# POWER_SENSING.net
KiCad netlist of a schematic drawn in Altium Designer
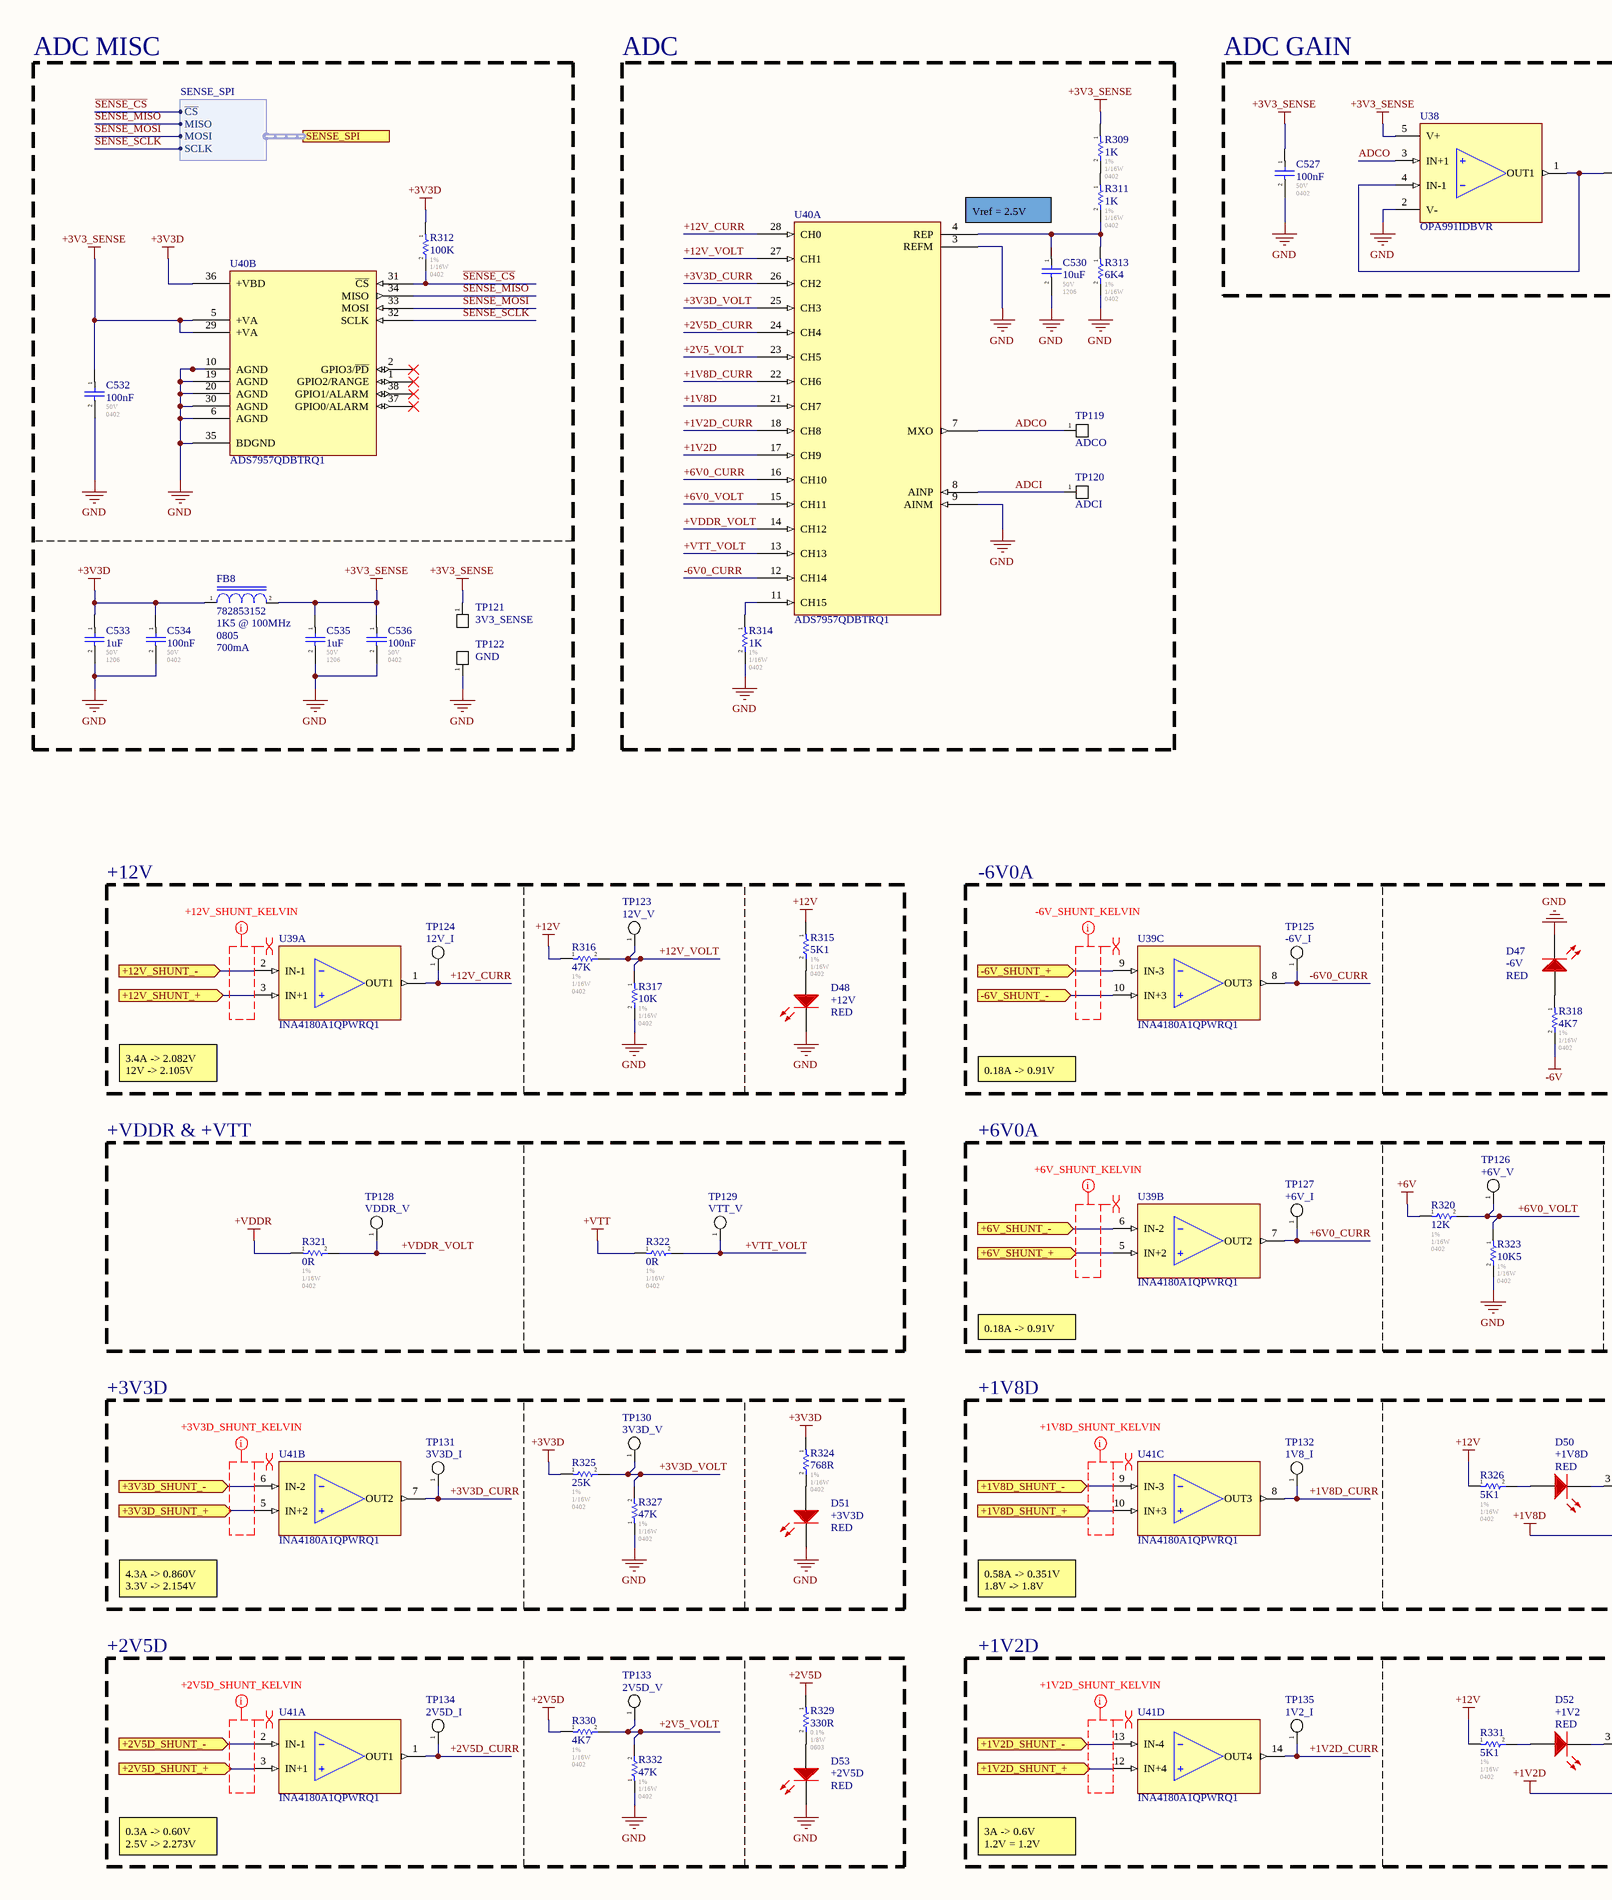
[diagram p0: POWER_SENSING.SchDoc, left]
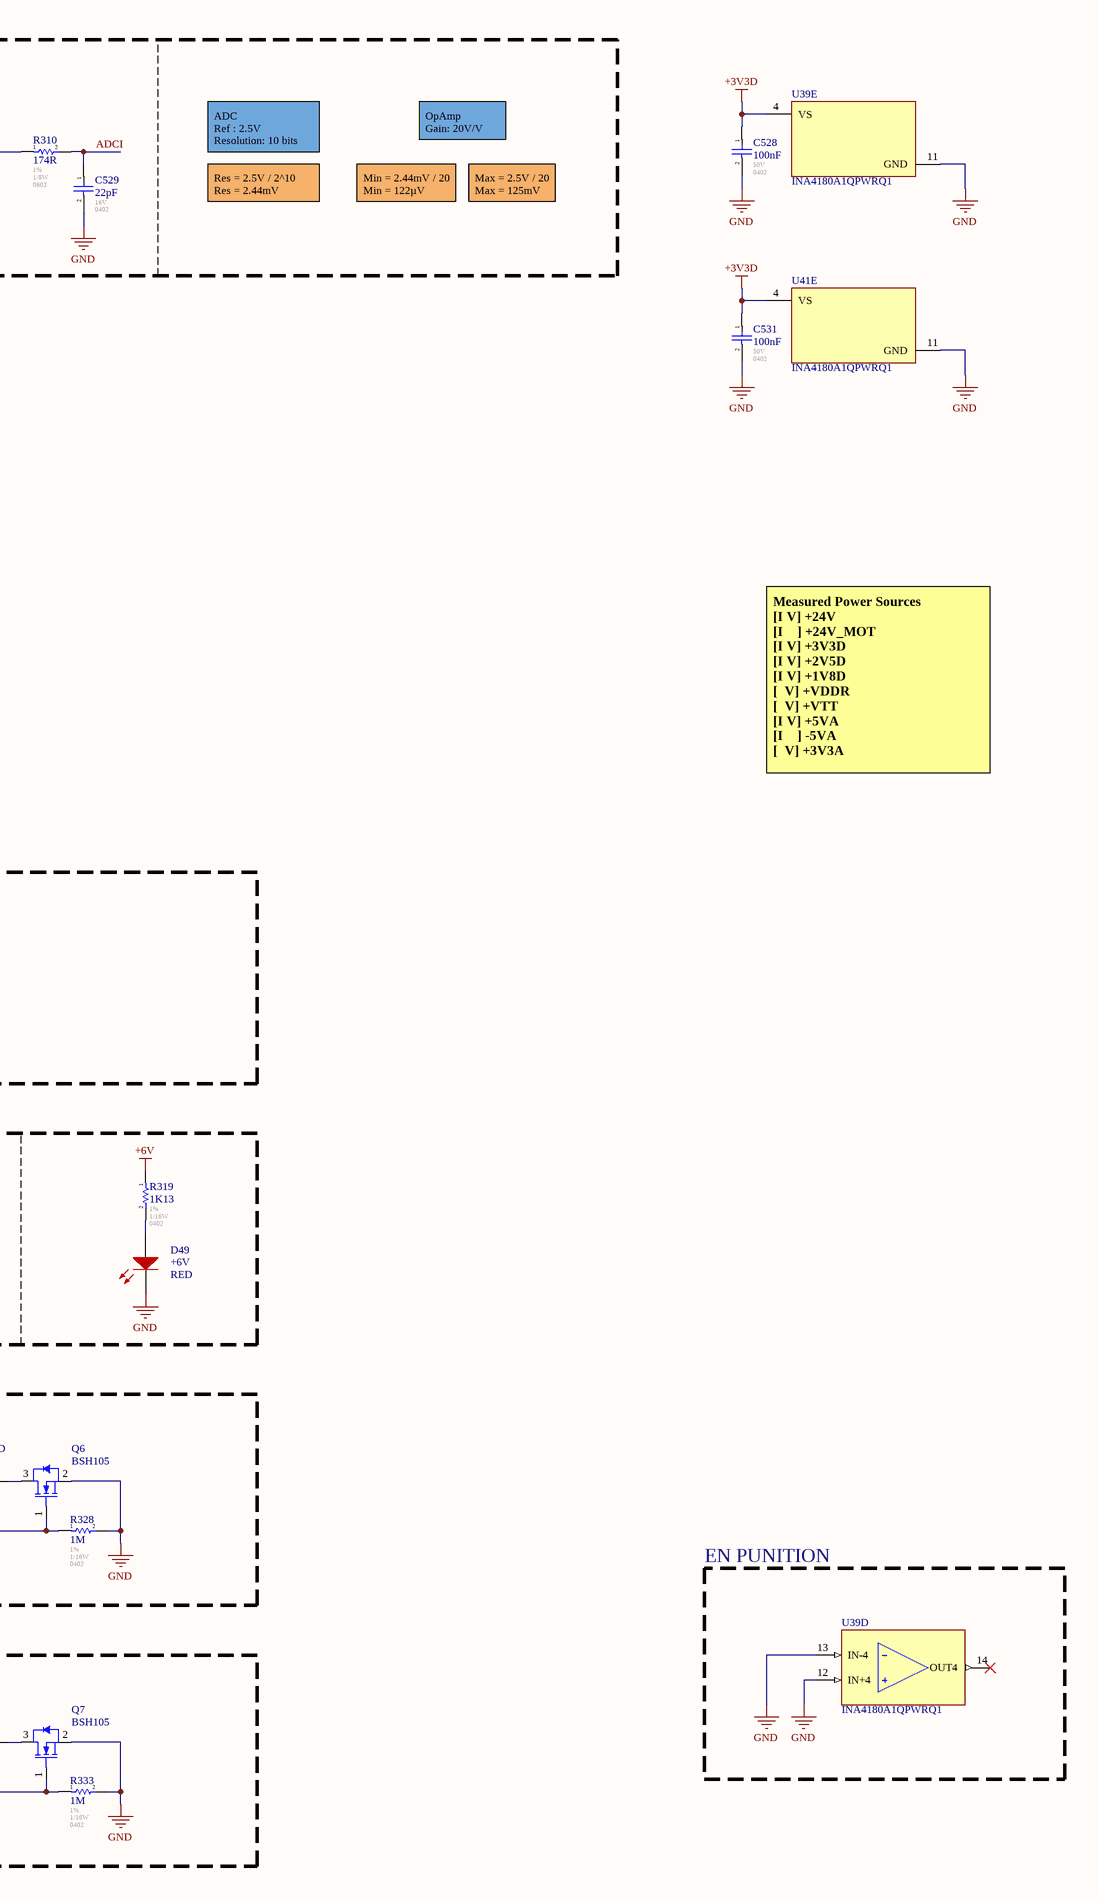
[diagram p1: POWER_SENSING.SchDoc, right]

(export (version "E")
  (design (tool "Eeschema 10.0.6"))
  (components
    (comp (ref "C527")
      (value "100nF")
      (footprint "0402")
      (description "GCM155R71H104KE02J\r\n0402 100nF 10% X7R Ceramic Capacitor")
      (fields
        (field (name "MFR") "Murata")
        (field (name "PART#") "GCM155R71H104KE02J")
        (field (name "VOLTAGE - RATED") "50V")
      )
      (libsource (lib "Symbols") (part "CAP_CER"))
    )
    (comp (ref "C528")
      (value "100nF")
      (footprint "0402")
      (description "GCM155R71H104KE02J\r\n0402 100nF 10% X7R Ceramic Capacitor")
      (fields
        (field (name "MFR") "Murata")
        (field (name "PART#") "GCM155R71H104KE02J")
        (field (name "VOLTAGE - RATED") "50V")
      )
      (libsource (lib "Symbols") (part "CAP_CER"))
    )
    (comp (ref "C529")
      (value "22pF")
      (footprint "0402")
      (description "0402 22pF 10% X7R 16V Ceramic Capacitor\r\nC0402C220K4RACAUTO")
      (fields
        (field (name "MFR") "KEMET")
        (field (name "PART#") "C0402C220K4RACAUTO")
        (field (name "VOLTAGE - RATED") "16V")
      )
      (libsource (lib "Symbols") (part "CAP_CER"))
    )
    (comp (ref "C530")
      (value "10uF")
      (footprint "1206")
      (description "GRT31CR61H106KE01L\r\n1206 10uF 10% X5R Ceramic Capacitor")
      (fields
        (field (name "MFR") "Murata")
        (field (name "VOLTAGE - RATED") "50V")
        (field (name "TOLERANCE") "10%")
      )
      (libsource (lib "Symbols") (part "CAP_CER"))
    )
    (comp (ref "C531")
      (value "100nF")
      (footprint "0402")
      (description "GCM155R71H104KE02J\r\n0402 100nF 10% X7R Ceramic Capacitor")
      (fields
        (field (name "MFR") "Murata")
        (field (name "PART#") "GCM155R71H104KE02J")
        (field (name "VOLTAGE - RATED") "50V")
      )
      (libsource (lib "Symbols") (part "CAP_CER"))
    )
    (comp (ref "C532")
      (value "100nF")
      (footprint "0402")
      (description "GCM155R71H104KE02J\r\n0402 100nF 10% X7R Ceramic Capacitor")
      (fields
        (field (name "MFR") "Murata")
        (field (name "PART#") "GCM155R71H104KE02J")
        (field (name "VOLTAGE - RATED") "50V")
      )
      (libsource (lib "Symbols") (part "CAP_CER"))
    )
    (comp (ref "C533")
      (value "1uF")
      (footprint "1206")
      (description "GCJ31CR71H105KA12L\r\n1206 1uF 10% X7R Ceramic Capacitor")
      (fields
        (field (name "MFR") "Murata")
        (field (name "PART#") "GCJ31CR71H105KA12L")
        (field (name "VOLTAGE - RATED") "50V")
      )
      (libsource (lib "Symbols") (part "CAP_CER"))
    )
    (comp (ref "C534")
      (value "100nF")
      (footprint "0402")
      (description "GCM155R71H104KE02J\r\n0402 100nF 10% X7R Ceramic Capacitor")
      (fields
        (field (name "MFR") "Murata")
        (field (name "PART#") "GCM155R71H104KE02J")
        (field (name "VOLTAGE - RATED") "50V")
      )
      (libsource (lib "Symbols") (part "CAP_CER"))
    )
    (comp (ref "C535")
      (value "1uF")
      (footprint "1206")
      (description "GCJ31CR71H105KA12L\r\n1206 1uF 10% X7R Ceramic Capacitor")
      (fields
        (field (name "MFR") "Murata")
        (field (name "PART#") "GCJ31CR71H105KA12L")
        (field (name "VOLTAGE - RATED") "50V")
      )
      (libsource (lib "Symbols") (part "CAP_CER"))
    )
    (comp (ref "C536")
      (value "100nF")
      (footprint "0402")
      (description "GCM155R71H104KE02J\r\n0402 100nF 10% X7R Ceramic Capacitor")
      (fields
        (field (name "MFR") "Murata")
        (field (name "PART#") "GCM155R71H104KE02J")
        (field (name "VOLTAGE - RATED") "50V")
      )
      (libsource (lib "Symbols") (part "CAP_CER"))
    )
    (comp (ref "D47")
      (value "-6V")
      (footprint "LED_0603")
      (description "LED - 620nM RED 2mA - 0603")
      (fields
        (field (name "VOLTAGE") "1.8V")
        (field (name "MFG") "ROHM Semiconductor")
        (field (name "ALTIUM_VALUE") "RED")
        (field (name "CREATEDBY") "Jonathan Bouchard")
      )
      (libsource (lib "S7CAS_LIB2023") (part "LED_SML-311UTT86"))
    )
    (comp (ref "D48")
      (value "+12V")
      (footprint "LED_0603")
      (description "LED - 620nM RED 2mA - 0603")
      (fields
        (field (name "VOLTAGE") "1.8V")
        (field (name "MFG") "ROHM Semiconductor")
        (field (name "ALTIUM_VALUE") "RED")
        (field (name "CREATEDBY") "Jonathan Bouchard")
      )
      (libsource (lib "S7CAS_LIB2023") (part "LED_SML-311UTT86"))
    )
    (comp (ref "D49")
      (value "+6V")
      (footprint "LED_0603")
      (description "LED - 620nM RED 2mA - 0603")
      (fields
        (field (name "VOLTAGE") "1.8V")
        (field (name "MFG") "ROHM Semiconductor")
        (field (name "ALTIUM_VALUE") "RED")
        (field (name "CREATEDBY") "Jonathan Bouchard")
      )
      (libsource (lib "S7CAS_LIB2023") (part "LED_SML-311UTT86"))
    )
    (comp (ref "D50")
      (value "+1V8D")
      (footprint "LED_0603")
      (description "LED - 620nM RED 2mA - 0603")
      (fields
        (field (name "VOLTAGE") "1.8V")
        (field (name "MFG") "ROHM Semiconductor")
        (field (name "ALTIUM_VALUE") "RED")
        (field (name "CREATEDBY") "Jonathan Bouchard")
      )
      (libsource (lib "S7CAS_LIB2023") (part "LED_SML-311UTT86"))
    )
    (comp (ref "D51")
      (value "+3V3D")
      (footprint "LED_0603")
      (description "LED - 620nM RED 2mA - 0603")
      (fields
        (field (name "VOLTAGE") "1.8V")
        (field (name "MFG") "ROHM Semiconductor")
        (field (name "ALTIUM_VALUE") "RED")
        (field (name "CREATEDBY") "Jonathan Bouchard")
      )
      (libsource (lib "S7CAS_LIB2023") (part "LED_SML-311UTT86"))
    )
    (comp (ref "D52")
      (value "+1V2")
      (footprint "LED_0603")
      (description "LED - 620nM RED 2mA - 0603")
      (fields
        (field (name "VOLTAGE") "1.8V")
        (field (name "MFG") "ROHM Semiconductor")
        (field (name "ALTIUM_VALUE") "RED")
        (field (name "CREATEDBY") "Jonathan Bouchard")
      )
      (libsource (lib "S7CAS_LIB2023") (part "LED_SML-311UTT86"))
    )
    (comp (ref "D53")
      (value "+2V5D")
      (footprint "LED_0603")
      (description "LED - 620nM RED 2mA - 0603")
      (fields
        (field (name "VOLTAGE") "1.8V")
        (field (name "MFG") "ROHM Semiconductor")
        (field (name "ALTIUM_VALUE") "RED")
        (field (name "CREATEDBY") "Jonathan Bouchard")
      )
      (libsource (lib "S7CAS_LIB2023") (part "LED_SML-311UTT86"))
    )
    (comp (ref "FB8")
      (value "782853152")
      (footprint "IND_0805")
      (description "600 Ohms @ 100 MHz 1 Signal Line Ferrite Bead 0603 (1608 Metric) 1A 200mOhm")
      (fields
        (field (name "IMPEDANCE @ FREQ") "1K5 @ 100MHz")
        (field (name "PACKAGE / CASE") "0805")
        (field (name "CURRENT RATING") "700mA")
        (field (name "MANUFACTURER") "Wurth Elektronik")
      )
      (libsource (lib "Symbols") (part "FERRITE_BEAD"))
    )
    (comp (ref "Q6")
      (value "BSH105")
      (footprint "SOT23-3")
      (fields
        (field (name "CREATEDBY/DATE") "Louis-Daniel Gaulin / 20-02-2020")
        (field (name "VERIFIEDBY") "C.Paulin - 21/02/2020")
      )
      (libsource (lib "S7CAS_LIB2023") (part "TRX_NMOS_SI2310-TP"))
    )
    (comp (ref "Q7")
      (value "BSH105")
      (footprint "SOT23-3")
      (fields
        (field (name "CREATEDBY/DATE") "Louis-Daniel Gaulin / 20-02-2020")
        (field (name "VERIFIEDBY") "C.Paulin - 21/02/2020")
      )
      (libsource (lib "S7CAS_LIB2023") (part "TRX_NMOS_SI2310-TP"))
    )
    (comp (ref "R309")
      (value "1K")
      (footprint "RES_0402")
      (fields
        (field (name "TOLERANCE") "1%")
        (field (name "POWER") "1/16W")
        (field (name "PACKAGE / CASE") "0402")
      )
      (libsource (lib "Symbols") (part "RESISTOR"))
    )
    (comp (ref "R310")
      (value "174R")
      (footprint "RES_0603")
      (fields
        (field (name "TOLERANCE") "1%")
        (field (name "POWER") "1/8W")
        (field (name "PACKAGE / CASE") "0603")
      )
      (libsource (lib "Symbols") (part "RESISTOR"))
    )
    (comp (ref "R311")
      (value "1K")
      (footprint "RES_0402")
      (fields
        (field (name "TOLERANCE") "1%")
        (field (name "POWER") "1/16W")
        (field (name "PACKAGE / CASE") "0402")
      )
      (libsource (lib "Symbols") (part "RESISTOR"))
    )
    (comp (ref "R312")
      (value "100K")
      (footprint "RES_0402")
      (fields
        (field (name "TOLERANCE") "1%")
        (field (name "POWER") "1/16W")
        (field (name "PACKAGE / CASE") "0402")
      )
      (libsource (lib "Symbols") (part "RESISTOR"))
    )
    (comp (ref "R313")
      (value "6K4")
      (footprint "RES_0402")
      (fields
        (field (name "TOLERANCE") "1%")
        (field (name "POWER") "1/16W")
        (field (name "PACKAGE / CASE") "0402")
      )
      (libsource (lib "Symbols") (part "RESISTOR"))
    )
    (comp (ref "R314")
      (value "1K")
      (footprint "RES_0402")
      (fields
        (field (name "TOLERANCE") "1%")
        (field (name "POWER") "1/16W")
        (field (name "PACKAGE / CASE") "0402")
      )
      (libsource (lib "Symbols") (part "RESISTOR"))
    )
    (comp (ref "R315")
      (value "5K1")
      (footprint "RES_0402")
      (fields
        (field (name "TOLERANCE") "1%")
        (field (name "POWER") "1/16W")
        (field (name "PACKAGE / CASE") "0402")
      )
      (libsource (lib "Symbols") (part "RESISTOR"))
    )
    (comp (ref "R316")
      (value "47K")
      (footprint "RES_0402")
      (fields
        (field (name "TOLERANCE") "1%")
        (field (name "POWER") "1/16W")
        (field (name "PACKAGE / CASE") "0402")
      )
      (libsource (lib "Symbols") (part "RESISTOR"))
    )
    (comp (ref "R317")
      (value "10K")
      (footprint "RES_0402")
      (fields
        (field (name "TOLERANCE") "1%")
        (field (name "POWER") "1/16W")
        (field (name "PACKAGE / CASE") "0402")
      )
      (libsource (lib "Symbols") (part "RESISTOR"))
    )
    (comp (ref "R318")
      (value "4K7")
      (footprint "RES_0402")
      (fields
        (field (name "TOLERANCE") "1%")
        (field (name "POWER") "1/16W")
        (field (name "PACKAGE / CASE") "0402")
      )
      (libsource (lib "Symbols") (part "RESISTOR"))
    )
    (comp (ref "R319")
      (value "1K13")
      (footprint "RES_0402")
      (fields
        (field (name "TOLERANCE") "1%")
        (field (name "POWER") "1/16W")
        (field (name "PACKAGE / CASE") "0402")
      )
      (libsource (lib "Symbols") (part "RESISTOR"))
    )
    (comp (ref "R320")
      (value "12K")
      (footprint "RES_0402")
      (fields
        (field (name "TOLERANCE") "1%")
        (field (name "POWER") "1/16W")
        (field (name "PACKAGE / CASE") "0402")
      )
      (libsource (lib "Symbols") (part "RESISTOR"))
    )
    (comp (ref "R321")
      (value "0R")
      (footprint "RES_0402")
      (fields
        (field (name "TOLERANCE") "1%")
        (field (name "POWER") "1/16W")
        (field (name "PACKAGE / CASE") "0402")
      )
      (libsource (lib "Symbols") (part "RESISTOR"))
    )
    (comp (ref "R322")
      (value "0R")
      (footprint "RES_0402")
      (fields
        (field (name "TOLERANCE") "1%")
        (field (name "POWER") "1/16W")
        (field (name "PACKAGE / CASE") "0402")
      )
      (libsource (lib "Symbols") (part "RESISTOR"))
    )
    (comp (ref "R323")
      (value "10K5")
      (footprint "RES_0402")
      (fields
        (field (name "TOLERANCE") "1%")
        (field (name "POWER") "1/16W")
        (field (name "PACKAGE / CASE") "0402")
      )
      (libsource (lib "Symbols") (part "RESISTOR"))
    )
    (comp (ref "R324")
      (value "768R")
      (footprint "RES_0402")
      (fields
        (field (name "TOLERANCE") "1%")
        (field (name "POWER") "1/16W")
        (field (name "PACKAGE / CASE") "0402")
      )
      (libsource (lib "Symbols") (part "RESISTOR"))
    )
    (comp (ref "R325")
      (value "25K")
      (footprint "RES_0402")
      (fields
        (field (name "TOLERANCE") "1%")
        (field (name "POWER") "1/16W")
        (field (name "PACKAGE / CASE") "0402")
      )
      (libsource (lib "Symbols") (part "RESISTOR"))
    )
    (comp (ref "R326")
      (value "5K1")
      (footprint "RES_0402")
      (fields
        (field (name "TOLERANCE") "1%")
        (field (name "POWER") "1/16W")
        (field (name "PACKAGE / CASE") "0402")
      )
      (libsource (lib "Symbols") (part "RESISTOR"))
    )
    (comp (ref "R327")
      (value "47K")
      (footprint "RES_0402")
      (fields
        (field (name "TOLERANCE") "1%")
        (field (name "POWER") "1/16W")
        (field (name "PACKAGE / CASE") "0402")
      )
      (libsource (lib "Symbols") (part "RESISTOR"))
    )
    (comp (ref "R328")
      (value "1M")
      (footprint "RES_0402")
      (description "1M 0402 1% 1/16W Resistor")
      (fields
        (field (name "TOLERANCE") "1%")
        (field (name "POWER") "1/16W")
        (field (name "PACKAGE / CASE") "0402")
      )
      (libsource (lib "Symbols") (part "RESISTOR"))
    )
    (comp (ref "R329")
      (value "330R")
      (footprint "RES_0603")
      (description "1M 0603 1% 1/16W Resistor")
      (fields
        (field (name "TOLERANCE") "0.1%")
        (field (name "POWER") "1/8W")
        (field (name "PACKAGE / CASE") "0603")
      )
      (libsource (lib "Symbols") (part "RESISTOR"))
    )
    (comp (ref "R330")
      (value "4K7")
      (footprint "RES_0402")
      (fields
        (field (name "TOLERANCE") "1%")
        (field (name "POWER") "1/16W")
        (field (name "PACKAGE / CASE") "0402")
      )
      (libsource (lib "Symbols") (part "RESISTOR"))
    )
    (comp (ref "R331")
      (value "5K1")
      (footprint "RES_0402")
      (fields
        (field (name "TOLERANCE") "1%")
        (field (name "POWER") "1/16W")
        (field (name "PACKAGE / CASE") "0402")
      )
      (libsource (lib "Symbols") (part "RESISTOR"))
    )
    (comp (ref "R332")
      (value "47K")
      (footprint "RES_0402")
      (fields
        (field (name "TOLERANCE") "1%")
        (field (name "POWER") "1/16W")
        (field (name "PACKAGE / CASE") "0402")
      )
      (libsource (lib "Symbols") (part "RESISTOR"))
    )
    (comp (ref "R333")
      (value "1M")
      (footprint "RES_0402")
      (description "1M 0402 1% 1/16W Resistor")
      (fields
        (field (name "TOLERANCE") "1%")
        (field (name "POWER") "1/16W")
        (field (name "PACKAGE / CASE") "0402")
      )
      (libsource (lib "Symbols") (part "RESISTOR"))
    )
    (comp (ref "TP119")
      (value "ADCO")
      (footprint "TP_PAD")
      (description "Test Point")
      (libsource (lib "Symbols") (part "TESTPOINT_PAD"))
    )
    (comp (ref "TP120")
      (value "ADCI")
      (footprint "TP_PAD")
      (description "Test Point")
      (libsource (lib "Symbols") (part "TESTPOINT_PAD"))
    )
    (comp (ref "TP121")
      (value "3V3_SENSE")
      (footprint "TP_PAD")
      (description "Test Point")
      (libsource (lib "Symbols") (part "TESTPOINT_PAD"))
    )
    (comp (ref "TP122")
      (value "GND")
      (footprint "TP_PAD")
      (description "Test Point")
      (libsource (lib "Symbols") (part "TESTPOINT_PAD"))
    )
    (comp (ref "TP123")
      (value "12V_V")
      (footprint "TP_PAD_SMALL")
      (description "Test Point")
      (libsource (lib "Symbols") (part "TESTPOINT_PAD_SMALL"))
    )
    (comp (ref "TP124")
      (value "12V_I")
      (footprint "TP_PAD_SMALL")
      (description "Test Point")
      (libsource (lib "Symbols") (part "TESTPOINT_PAD_SMALL"))
    )
    (comp (ref "TP125")
      (value "-6V_I")
      (footprint "TP_PAD_SMALL")
      (description "Test Point")
      (libsource (lib "Symbols") (part "TESTPOINT_PAD_SMALL"))
    )
    (comp (ref "TP126")
      (value "+6V_V")
      (footprint "TP_PAD_SMALL")
      (description "Test Point")
      (libsource (lib "Symbols") (part "TESTPOINT_PAD_SMALL"))
    )
    (comp (ref "TP127")
      (value "+6V_I")
      (footprint "TP_PAD_SMALL")
      (description "Test Point")
      (libsource (lib "Symbols") (part "TESTPOINT_PAD_SMALL"))
    )
    (comp (ref "TP128")
      (value "VDDR_V")
      (footprint "TP_PAD_SMALL")
      (description "Test Point")
      (libsource (lib "Symbols") (part "TESTPOINT_PAD_SMALL"))
    )
    (comp (ref "TP129")
      (value "VTT_V")
      (footprint "TP_PAD_SMALL")
      (description "Test Point")
      (libsource (lib "Symbols") (part "TESTPOINT_PAD_SMALL"))
    )
    (comp (ref "TP130")
      (value "3V3D_V")
      (footprint "TP_PAD_SMALL")
      (description "Test Point")
      (libsource (lib "Symbols") (part "TESTPOINT_PAD_SMALL"))
    )
    (comp (ref "TP131")
      (value "3V3D_I")
      (footprint "TP_PAD_SMALL")
      (description "Test Point")
      (libsource (lib "Symbols") (part "TESTPOINT_PAD_SMALL"))
    )
    (comp (ref "TP132")
      (value "1V8_I")
      (footprint "TP_PAD_SMALL")
      (description "Test Point")
      (libsource (lib "Symbols") (part "TESTPOINT_PAD_SMALL"))
    )
    (comp (ref "TP133")
      (value "2V5D_V")
      (footprint "TP_PAD_SMALL")
      (description "Test Point")
      (libsource (lib "Symbols") (part "TESTPOINT_PAD_SMALL"))
    )
    (comp (ref "TP134")
      (value "2V5D_I")
      (footprint "TP_PAD_SMALL")
      (description "Test Point")
      (libsource (lib "Symbols") (part "TESTPOINT_PAD_SMALL"))
    )
    (comp (ref "TP135")
      (value "1V2_I")
      (footprint "TP_PAD_SMALL")
      (description "Test Point")
      (libsource (lib "Symbols") (part "TESTPOINT_PAD_SMALL"))
    )
    (comp (ref "U38")
      (value "OPA991IDBVR")
      (footprint "SOT23-5")
      (description "General Purpose Amplifier 1 Circuit Rail-to-Rail SOT-23-5")
      (fields (field (name "MFR") "Texas Instruments"))
      (libsource (lib "Misc") (part "OPA991IDBVR"))
    )
    (comp (ref "U39")
      (value "INA4180A1QPWRQ1")
      (footprint "TSSOP-14_4.4MM")
      (description "Current Sense Amplifier 4 Circuit Differential, Rail-to-Rail 14-TSSOP")
      (fields (field (name "MFR") "Texas Instruments"))
      (libsource (lib "Misc") (part "INA4180A1QPWRQ1"))
    )
    (comp (ref "U40")
      (value "ADS7957QDBTRQ1")
      (footprint "TSSOP-38_4.4MM")
      (description "10 Bit Analog to Digital Converter 16 Input 1 SAR 38-TSSOP")
      (fields (field (name "MFR") "Texas Instruments"))
      (libsource (lib "Misc") (part "ADS7957QDBTRQ1"))
    )
    (comp (ref "U41")
      (value "INA4180A1QPWRQ1")
      (footprint "TSSOP-14_4.4MM")
      (description "Current Sense Amplifier 4 Circuit Differential, Rail-to-Rail 14-TSSOP")
      (fields (field (name "MFR") "Texas Instruments"))
      (libsource (lib "Misc") (part "INA4180A1QPWRQ1"))
    )
  )
  (nets
    (net (code "2") (name "+1V2D") (class "Default")
      (node (ref "Q7") (pin "1") (pinfunction "G_1") (pintype "passive"))
      (node (ref "R333") (pin "1") (pinfunction "1_1") (pintype "passive"))
      (node (ref "U40") (pin "17") (pinfunction "CH9_17") (pintype "input"))
    )
    (net (code "3") (name "+1V8D") (class "Default")
      (node (ref "Q6") (pin "1") (pinfunction "G_1") (pintype "passive"))
      (node (ref "R328") (pin "1") (pinfunction "1_1") (pintype "passive"))
      (node (ref "U40") (pin "21") (pinfunction "CH7_21") (pintype "input"))
    )
    (net (code "4") (name "+2V5D") (class "Default")
      (node (ref "R329") (pin "1") (pinfunction "1_1") (pintype "passive"))
      (node (ref "R330") (pin "1") (pinfunction "1_1") (pintype "passive"))
    )
    (net (code "5") (name "+3V3D") (class "Default")
      (node (ref "C528") (pin "1") (pinfunction "1_1") (pintype "passive"))
      (node (ref "C531") (pin "1") (pinfunction "1_1") (pintype "passive"))
      (node (ref "C533") (pin "1") (pinfunction "1_1") (pintype "passive"))
      (node (ref "C534") (pin "1") (pinfunction "1_1") (pintype "passive"))
      (node (ref "FB8") (pin "1") (pinfunction "1_1") (pintype "passive"))
      (node (ref "R312") (pin "1") (pinfunction "1_1") (pintype "passive"))
      (node (ref "R324") (pin "1") (pinfunction "1_1") (pintype "passive"))
      (node (ref "R325") (pin "1") (pinfunction "1_1") (pintype "passive"))
      (node (ref "U39") (pin "4") (pinfunction "VS_4") (pintype "power_in"))
      (node (ref "U40") (pin "36") (pinfunction "+VBD_36") (pintype "power_in"))
      (node (ref "U41") (pin "4") (pinfunction "VS_4") (pintype "power_in"))
    )
    (net (code "6") (name "+3V3_SENSE") (class "Default")
      (node (ref "C527") (pin "1") (pinfunction "1_1") (pintype "passive"))
      (node (ref "C532") (pin "1") (pinfunction "1_1") (pintype "passive"))
      (node (ref "C535") (pin "1") (pinfunction "1_1") (pintype "passive"))
      (node (ref "C536") (pin "1") (pinfunction "1_1") (pintype "passive"))
      (node (ref "FB8") (pin "2") (pinfunction "2_2") (pintype "passive"))
      (node (ref "R309") (pin "1") (pinfunction "1_1") (pintype "passive"))
      (node (ref "TP121") (pin "1") (pinfunction "A_1") (pintype "passive"))
      (node (ref "U38") (pin "5") (pinfunction "V+_5") (pintype "power_in"))
      (node (ref "U40") (pin "29") (pinfunction "+VA_29") (pintype "power_in"))
      (node (ref "U40") (pin "5") (pinfunction "+VA_5") (pintype "power_in"))
    )
    (net (code "7") (name "+6V") (class "Default")
      (node (ref "R319") (pin "1") (pinfunction "1_1") (pintype "passive"))
      (node (ref "R320") (pin "1") (pinfunction "1_1") (pintype "passive"))
    )
    (net (code "8") (name "+12V") (class "Default")
      (node (ref "R315") (pin "1") (pinfunction "1_1") (pintype "passive"))
      (node (ref "R316") (pin "1") (pinfunction "1_1") (pintype "passive"))
      (node (ref "R326") (pin "1") (pinfunction "1_1") (pintype "passive"))
      (node (ref "R331") (pin "1") (pinfunction "1_1") (pintype "passive"))
    )
    (net (code "9") (name "+VDDR") (class "Default")
      (node (ref "R321") (pin "1") (pinfunction "1_1") (pintype "passive"))
    )
    (net (code "10") (name "+VTT") (class "Default")
      (node (ref "R322") (pin "1") (pinfunction "1_1") (pintype "passive"))
    )
    (net (code "11") (name "-6V") (class "Default")
      (node (ref "R318") (pin "2") (pinfunction "2_2") (pintype "passive"))
    )
    (net (code "12") (name "/+1V2D_CURR") (class "Default")
      (node (ref "TP135") (pin "1") (pinfunction "A_1") (pintype "passive"))
      (node (ref "U40") (pin "18") (pinfunction "CH8_18") (pintype "input"))
      (node (ref "U41") (pin "14") (pinfunction "OUT4_14") (pintype "output"))
    )
    (net (code "13") (name "/+1V2D_SHUNT_+") (class "Default")
      (node (ref "U41") (pin "12") (pinfunction "IN+4_12") (pintype "input"))
    )
    (net (code "14") (name "/+1V2D_SHUNT_-") (class "Default")
      (node (ref "U41") (pin "13") (pinfunction "IN-4_13") (pintype "input"))
    )
    (net (code "15") (name "/+1V8D_CURR") (class "Default")
      (node (ref "TP132") (pin "1") (pinfunction "A_1") (pintype "passive"))
      (node (ref "U40") (pin "22") (pinfunction "CH6_22") (pintype "input"))
      (node (ref "U41") (pin "8") (pinfunction "OUT3_8") (pintype "output"))
    )
    (net (code "16") (name "/+1V8D_SHUNT_+") (class "Default")
      (node (ref "U41") (pin "10") (pinfunction "IN+3_10") (pintype "input"))
    )
    (net (code "17") (name "/+1V8D_SHUNT_-") (class "Default")
      (node (ref "U41") (pin "9") (pinfunction "IN-3_9") (pintype "input"))
    )
    (net (code "18") (name "/+2V5D_CURR") (class "Default")
      (node (ref "TP134") (pin "1") (pinfunction "A_1") (pintype "passive"))
      (node (ref "U40") (pin "24") (pinfunction "CH4_24") (pintype "input"))
      (node (ref "U41") (pin "1") (pinfunction "OUT1_1") (pintype "output"))
    )
    (net (code "19") (name "/+2V5D_SHUNT_+") (class "Default")
      (node (ref "U41") (pin "3") (pinfunction "IN+1_3") (pintype "input"))
    )
    (net (code "20") (name "/+2V5D_SHUNT_-") (class "Default")
      (node (ref "U41") (pin "2") (pinfunction "IN-1_2") (pintype "input"))
    )
    (net (code "21") (name "/+2V5_VOLT") (class "Default")
      (node (ref "R330") (pin "2") (pinfunction "2_2") (pintype "passive"))
      (node (ref "R332") (pin "2") (pinfunction "2_2") (pintype "passive"))
      (node (ref "TP133") (pin "1") (pinfunction "A_1") (pintype "passive"))
      (node (ref "U40") (pin "23") (pinfunction "CH5_23") (pintype "input"))
    )
    (net (code "22") (name "/+3V3D_CURR") (class "Default")
      (node (ref "TP131") (pin "1") (pinfunction "A_1") (pintype "passive"))
      (node (ref "U40") (pin "26") (pinfunction "CH2_26") (pintype "input"))
      (node (ref "U41") (pin "7") (pinfunction "OUT2_7") (pintype "output"))
    )
    (net (code "23") (name "/+3V3D_SHUNT_+") (class "Default")
      (node (ref "U41") (pin "5") (pinfunction "IN+2_5") (pintype "input"))
    )
    (net (code "24") (name "/+3V3D_SHUNT_-") (class "Default")
      (node (ref "U41") (pin "6") (pinfunction "IN-2_6") (pintype "input"))
    )
    (net (code "25") (name "/+3V3D_VOLT") (class "Default")
      (node (ref "R325") (pin "2") (pinfunction "2_2") (pintype "passive"))
      (node (ref "R327") (pin "2") (pinfunction "2_2") (pintype "passive"))
      (node (ref "TP130") (pin "1") (pinfunction "A_1") (pintype "passive"))
      (node (ref "U40") (pin "25") (pinfunction "CH3_25") (pintype "input"))
    )
    (net (code "26") (name "/+6V0_CURR") (class "Default")
      (node (ref "TP127") (pin "1") (pinfunction "A_1") (pintype "passive"))
      (node (ref "U39") (pin "7") (pinfunction "OUT2_7") (pintype "output"))
      (node (ref "U40") (pin "16") (pinfunction "CH10_16") (pintype "input"))
    )
    (net (code "27") (name "/+6V0_VOLT") (class "Default")
      (node (ref "R320") (pin "2") (pinfunction "2_2") (pintype "passive"))
      (node (ref "R323") (pin "1") (pinfunction "1_1") (pintype "passive"))
      (node (ref "TP126") (pin "1") (pinfunction "A_1") (pintype "passive"))
      (node (ref "U40") (pin "15") (pinfunction "CH11_15") (pintype "input"))
    )
    (net (code "28") (name "/+6V_SHUNT_+") (class "Default")
      (node (ref "U39") (pin "5") (pinfunction "IN+2_5") (pintype "input"))
    )
    (net (code "29") (name "/+6V_SHUNT_-") (class "Default")
      (node (ref "U39") (pin "6") (pinfunction "IN-2_6") (pintype "input"))
    )
    (net (code "30") (name "/+12V_CURR") (class "Default")
      (node (ref "TP124") (pin "1") (pinfunction "A_1") (pintype "passive"))
      (node (ref "U39") (pin "1") (pinfunction "OUT1_1") (pintype "output"))
      (node (ref "U40") (pin "28") (pinfunction "CH0_28") (pintype "input"))
    )
    (net (code "31") (name "/+12V_SHUNT_+") (class "Default")
      (node (ref "U39") (pin "3") (pinfunction "IN+1_3") (pintype "input"))
    )
    (net (code "32") (name "/+12V_SHUNT_-") (class "Default")
      (node (ref "U39") (pin "2") (pinfunction "IN-1_2") (pintype "input"))
    )
    (net (code "33") (name "/+12V_VOLT") (class "Default")
      (node (ref "R316") (pin "2") (pinfunction "2_2") (pintype "passive"))
      (node (ref "R317") (pin "1") (pinfunction "1_1") (pintype "passive"))
      (node (ref "TP123") (pin "1") (pinfunction "A_1") (pintype "passive"))
      (node (ref "U40") (pin "27") (pinfunction "CH1_27") (pintype "input"))
    )
    (net (code "34") (name "/+VDDR_VOLT") (class "Default")
      (node (ref "R321") (pin "2") (pinfunction "2_2") (pintype "passive"))
      (node (ref "TP128") (pin "1") (pinfunction "A_1") (pintype "passive"))
      (node (ref "U40") (pin "14") (pinfunction "CH12_14") (pintype "input"))
    )
    (net (code "35") (name "/+VTT_VOLT") (class "Default")
      (node (ref "R322") (pin "2") (pinfunction "2_2") (pintype "passive"))
      (node (ref "TP129") (pin "1") (pinfunction "A_1") (pintype "passive"))
      (node (ref "U40") (pin "13") (pinfunction "CH13_13") (pintype "input"))
    )
    (net (code "36") (name "/-6V0_CURR") (class "Default")
      (node (ref "TP125") (pin "1") (pinfunction "A_1") (pintype "passive"))
      (node (ref "U39") (pin "8") (pinfunction "OUT3_8") (pintype "output"))
      (node (ref "U40") (pin "12") (pinfunction "CH14_12") (pintype "input"))
    )
    (net (code "37") (name "/-6V_SHUNT_+") (class "Default")
      (node (ref "U39") (pin "9") (pinfunction "IN-3_9") (pintype "input"))
    )
    (net (code "38") (name "/-6V_SHUNT_-") (class "Default")
      (node (ref "U39") (pin "10") (pinfunction "IN+3_10") (pintype "input"))
    )
    (net (code "39") (name "/ADCI") (class "Default")
      (node (ref "C529") (pin "1") (pinfunction "1_1") (pintype "passive"))
      (node (ref "R310") (pin "2") (pinfunction "2_2") (pintype "passive"))
      (node (ref "TP120") (pin "1") (pinfunction "A_1") (pintype "passive"))
      (node (ref "U40") (pin "8") (pinfunction "AINP_8") (pintype "input"))
    )
    (net (code "40") (name "/ADCO") (class "Default")
      (node (ref "TP119") (pin "1") (pinfunction "A_1") (pintype "passive"))
      (node (ref "U38") (pin "3") (pinfunction "IN+1_3") (pintype "input"))
      (node (ref "U40") (pin "7") (pinfunction "MXO_7") (pintype "output"))
    )
    (net (code "41") (name "/SENSE_CS") (class "Default")
      (node (ref "R312") (pin "2") (pinfunction "2_2") (pintype "passive"))
      (node (ref "U40") (pin "31") (pinfunction "CS_31") (pintype "input"))
    )
    (net (code "42") (name "/SENSE_MISO") (class "Default")
      (node (ref "U40") (pin "34") (pinfunction "MISO_34") (pintype "output"))
    )
    (net (code "43") (name "/SENSE_MOSI") (class "Default")
      (node (ref "U40") (pin "33") (pinfunction "MOSI_33") (pintype "input"))
    )
    (net (code "44") (name "/SENSE_SCLK") (class "Default")
      (node (ref "U40") (pin "32") (pinfunction "SCLK_32") (pintype "input"))
    )
    (net (code "46") (name "GND") (class "Default")
      (node (ref "C527") (pin "2") (pinfunction "2_2") (pintype "passive"))
      (node (ref "C528") (pin "2") (pinfunction "2_2") (pintype "passive"))
      (node (ref "C529") (pin "2") (pinfunction "2_2") (pintype "passive"))
      (node (ref "C530") (pin "2") (pinfunction "2_2") (pintype "passive"))
      (node (ref "C531") (pin "2") (pinfunction "2_2") (pintype "passive"))
      (node (ref "C532") (pin "2") (pinfunction "2_2") (pintype "passive"))
      (node (ref "C533") (pin "2") (pinfunction "2_2") (pintype "passive"))
      (node (ref "C534") (pin "2") (pinfunction "2_2") (pintype "passive"))
      (node (ref "C535") (pin "2") (pinfunction "2_2") (pintype "passive"))
      (node (ref "C536") (pin "2") (pinfunction "2_2") (pintype "passive"))
      (node (ref "D47") (pin "2") (pinfunction "K_2") (pintype "passive"))
      (node (ref "D48") (pin "2") (pinfunction "K_2") (pintype "passive"))
      (node (ref "D49") (pin "2") (pinfunction "K_2") (pintype "passive"))
      (node (ref "D51") (pin "2") (pinfunction "K_2") (pintype "passive"))
      (node (ref "D53") (pin "2") (pinfunction "K_2") (pintype "passive"))
      (node (ref "Q6") (pin "2") (pinfunction "S_2") (pintype "passive"))
      (node (ref "Q7") (pin "2") (pinfunction "S_2") (pintype "passive"))
      (node (ref "R313") (pin "2") (pinfunction "2_2") (pintype "passive"))
      (node (ref "R314") (pin "2") (pinfunction "2_2") (pintype "passive"))
      (node (ref "R317") (pin "2") (pinfunction "2_2") (pintype "passive"))
      (node (ref "R323") (pin "2") (pinfunction "2_2") (pintype "passive"))
      (node (ref "R327") (pin "1") (pinfunction "1_1") (pintype "passive"))
      (node (ref "R328") (pin "2") (pinfunction "2_2") (pintype "passive"))
      (node (ref "R332") (pin "1") (pinfunction "1_1") (pintype "passive"))
      (node (ref "R333") (pin "2") (pinfunction "2_2") (pintype "passive"))
      (node (ref "TP122") (pin "1") (pinfunction "A_1") (pintype "passive"))
      (node (ref "U38") (pin "2") (pinfunction "V-_2") (pintype "power_in"))
      (node (ref "U39") (pin "11") (pinfunction "GND_11") (pintype "power_in"))
      (node (ref "U39") (pin "12") (pinfunction "IN+4_12") (pintype "input"))
      (node (ref "U39") (pin "13") (pinfunction "IN-4_13") (pintype "input"))
      (node (ref "U40") (pin "10") (pinfunction "AGND_10") (pintype "power_in"))
      (node (ref "U40") (pin "19") (pinfunction "AGND_19") (pintype "power_in"))
      (node (ref "U40") (pin "20") (pinfunction "AGND_20") (pintype "power_in"))
      (node (ref "U40") (pin "3") (pinfunction "REFM_3") (pintype "power_in"))
      (node (ref "U40") (pin "30") (pinfunction "AGND_30") (pintype "power_in"))
      (node (ref "U40") (pin "35") (pinfunction "BDGND_35") (pintype "power_in"))
      (node (ref "U40") (pin "6") (pinfunction "AGND_6") (pintype "power_in"))
      (node (ref "U40") (pin "9") (pinfunction "AINM_9") (pintype "input"))
      (node (ref "U41") (pin "11") (pinfunction "GND_11") (pintype "power_in"))
    )
    (net (code "47") (name "Net-(D47-A)") (class "Default")
      (node (ref "D47") (pin "1") (pinfunction "A_1") (pintype "passive"))
      (node (ref "R318") (pin "1") (pinfunction "1_1") (pintype "passive"))
    )
    (net (code "48") (name "Net-(D48-A)") (class "Default")
      (node (ref "D48") (pin "1") (pinfunction "A_1") (pintype "passive"))
      (node (ref "R315") (pin "2") (pinfunction "2_2") (pintype "passive"))
    )
    (net (code "49") (name "Net-(D49-A)") (class "Default")
      (node (ref "D49") (pin "1") (pinfunction "A_1") (pintype "passive"))
      (node (ref "R319") (pin "2") (pinfunction "2_2") (pintype "passive"))
    )
    (net (code "50") (name "Net-(D50-A)") (class "Default")
      (node (ref "D50") (pin "1") (pinfunction "A_1") (pintype "passive"))
      (node (ref "R326") (pin "2") (pinfunction "2_2") (pintype "passive"))
    )
    (net (code "51") (name "Net-(D50-K)") (class "Default")
      (node (ref "D50") (pin "2") (pinfunction "K_2") (pintype "passive"))
      (node (ref "Q6") (pin "3") (pinfunction "D_3") (pintype "passive"))
    )
    (net (code "52") (name "Net-(D51-A)") (class "Default")
      (node (ref "D51") (pin "1") (pinfunction "A_1") (pintype "passive"))
      (node (ref "R324") (pin "2") (pinfunction "2_2") (pintype "passive"))
    )
    (net (code "53") (name "Net-(D52-A)") (class "Default")
      (node (ref "D52") (pin "1") (pinfunction "A_1") (pintype "passive"))
      (node (ref "R331") (pin "2") (pinfunction "2_2") (pintype "passive"))
    )
    (net (code "54") (name "Net-(D52-K)") (class "Default")
      (node (ref "D52") (pin "2") (pinfunction "K_2") (pintype "passive"))
      (node (ref "Q7") (pin "3") (pinfunction "D_3") (pintype "passive"))
    )
    (net (code "55") (name "Net-(D53-A)") (class "Default")
      (node (ref "D53") (pin "1") (pinfunction "A_1") (pintype "passive"))
      (node (ref "R329") (pin "2") (pinfunction "2_2") (pintype "passive"))
    )
    (net (code "56") (name "Net-(R309-Pad2)") (class "Default")
      (node (ref "R309") (pin "2") (pinfunction "2_2") (pintype "passive"))
      (node (ref "R311") (pin "1") (pinfunction "1_1") (pintype "passive"))
    )
    (net (code "57") (name "Net-(U38-IN-1)") (class "Default")
      (node (ref "R310") (pin "1") (pinfunction "1_1") (pintype "passive"))
      (node (ref "U38") (pin "1") (pinfunction "OUT1_1") (pintype "output"))
      (node (ref "U38") (pin "4") (pinfunction "IN-1_4") (pintype "input"))
    )
    (net (code "58") (name "Net-(U40A-CH15)") (class "Default")
      (node (ref "R314") (pin "1") (pinfunction "1_1") (pintype "passive"))
      (node (ref "U40") (pin "11") (pinfunction "CH15_11") (pintype "input"))
    )
    (net (code "59") (name "Net-(U40A-REP)") (class "Default")
      (node (ref "C530") (pin "1") (pinfunction "1_1") (pintype "passive"))
      (node (ref "R311") (pin "2") (pinfunction "2_2") (pintype "passive"))
      (node (ref "R313") (pin "1") (pinfunction "1_1") (pintype "passive"))
      (node (ref "U40") (pin "4") (pinfunction "REP_4") (pintype "power_in"))
    )
    (net (code "60") (name "unconnected-(U39D-OUT4-Pad14)") (class "Default")
      (node (ref "U39") (pin "14") (pinfunction "OUT4_14") (pintype "output+no_connect"))
    )
    (net (code "61") (name "unconnected-(U40B-GPIO0{slash}ALARM-Pad37)") (class "Default")
      (node (ref "U40") (pin "37") (pinfunction "GPIO0/ALARM_37") (pintype "bidirectional+no_connect"))
    )
    (net (code "62") (name "unconnected-(U40B-GPIO1{slash}ALARM-Pad38)") (class "Default")
      (node (ref "U40") (pin "38") (pinfunction "GPIO1/ALARM_38") (pintype "bidirectional+no_connect"))
    )
    (net (code "63") (name "unconnected-(U40B-GPIO2{slash}RANGE-Pad1)") (class "Default")
      (node (ref "U40") (pin "1") (pinfunction "GPIO2/RANGE_1") (pintype "bidirectional+no_connect"))
    )
    (net (code "64") (name "unconnected-(U40B-GPIO3{slash}~{PD}-Pad2)") (class "Default")
      (node (ref "U40") (pin "2") (pinfunction "GPIO3/~{PD}_2") (pintype "bidirectional+no_connect"))
    )
  )
)
